# 1-Schematic_PCB.net
KiCad netlist of a schematic drawn in EasyEDA
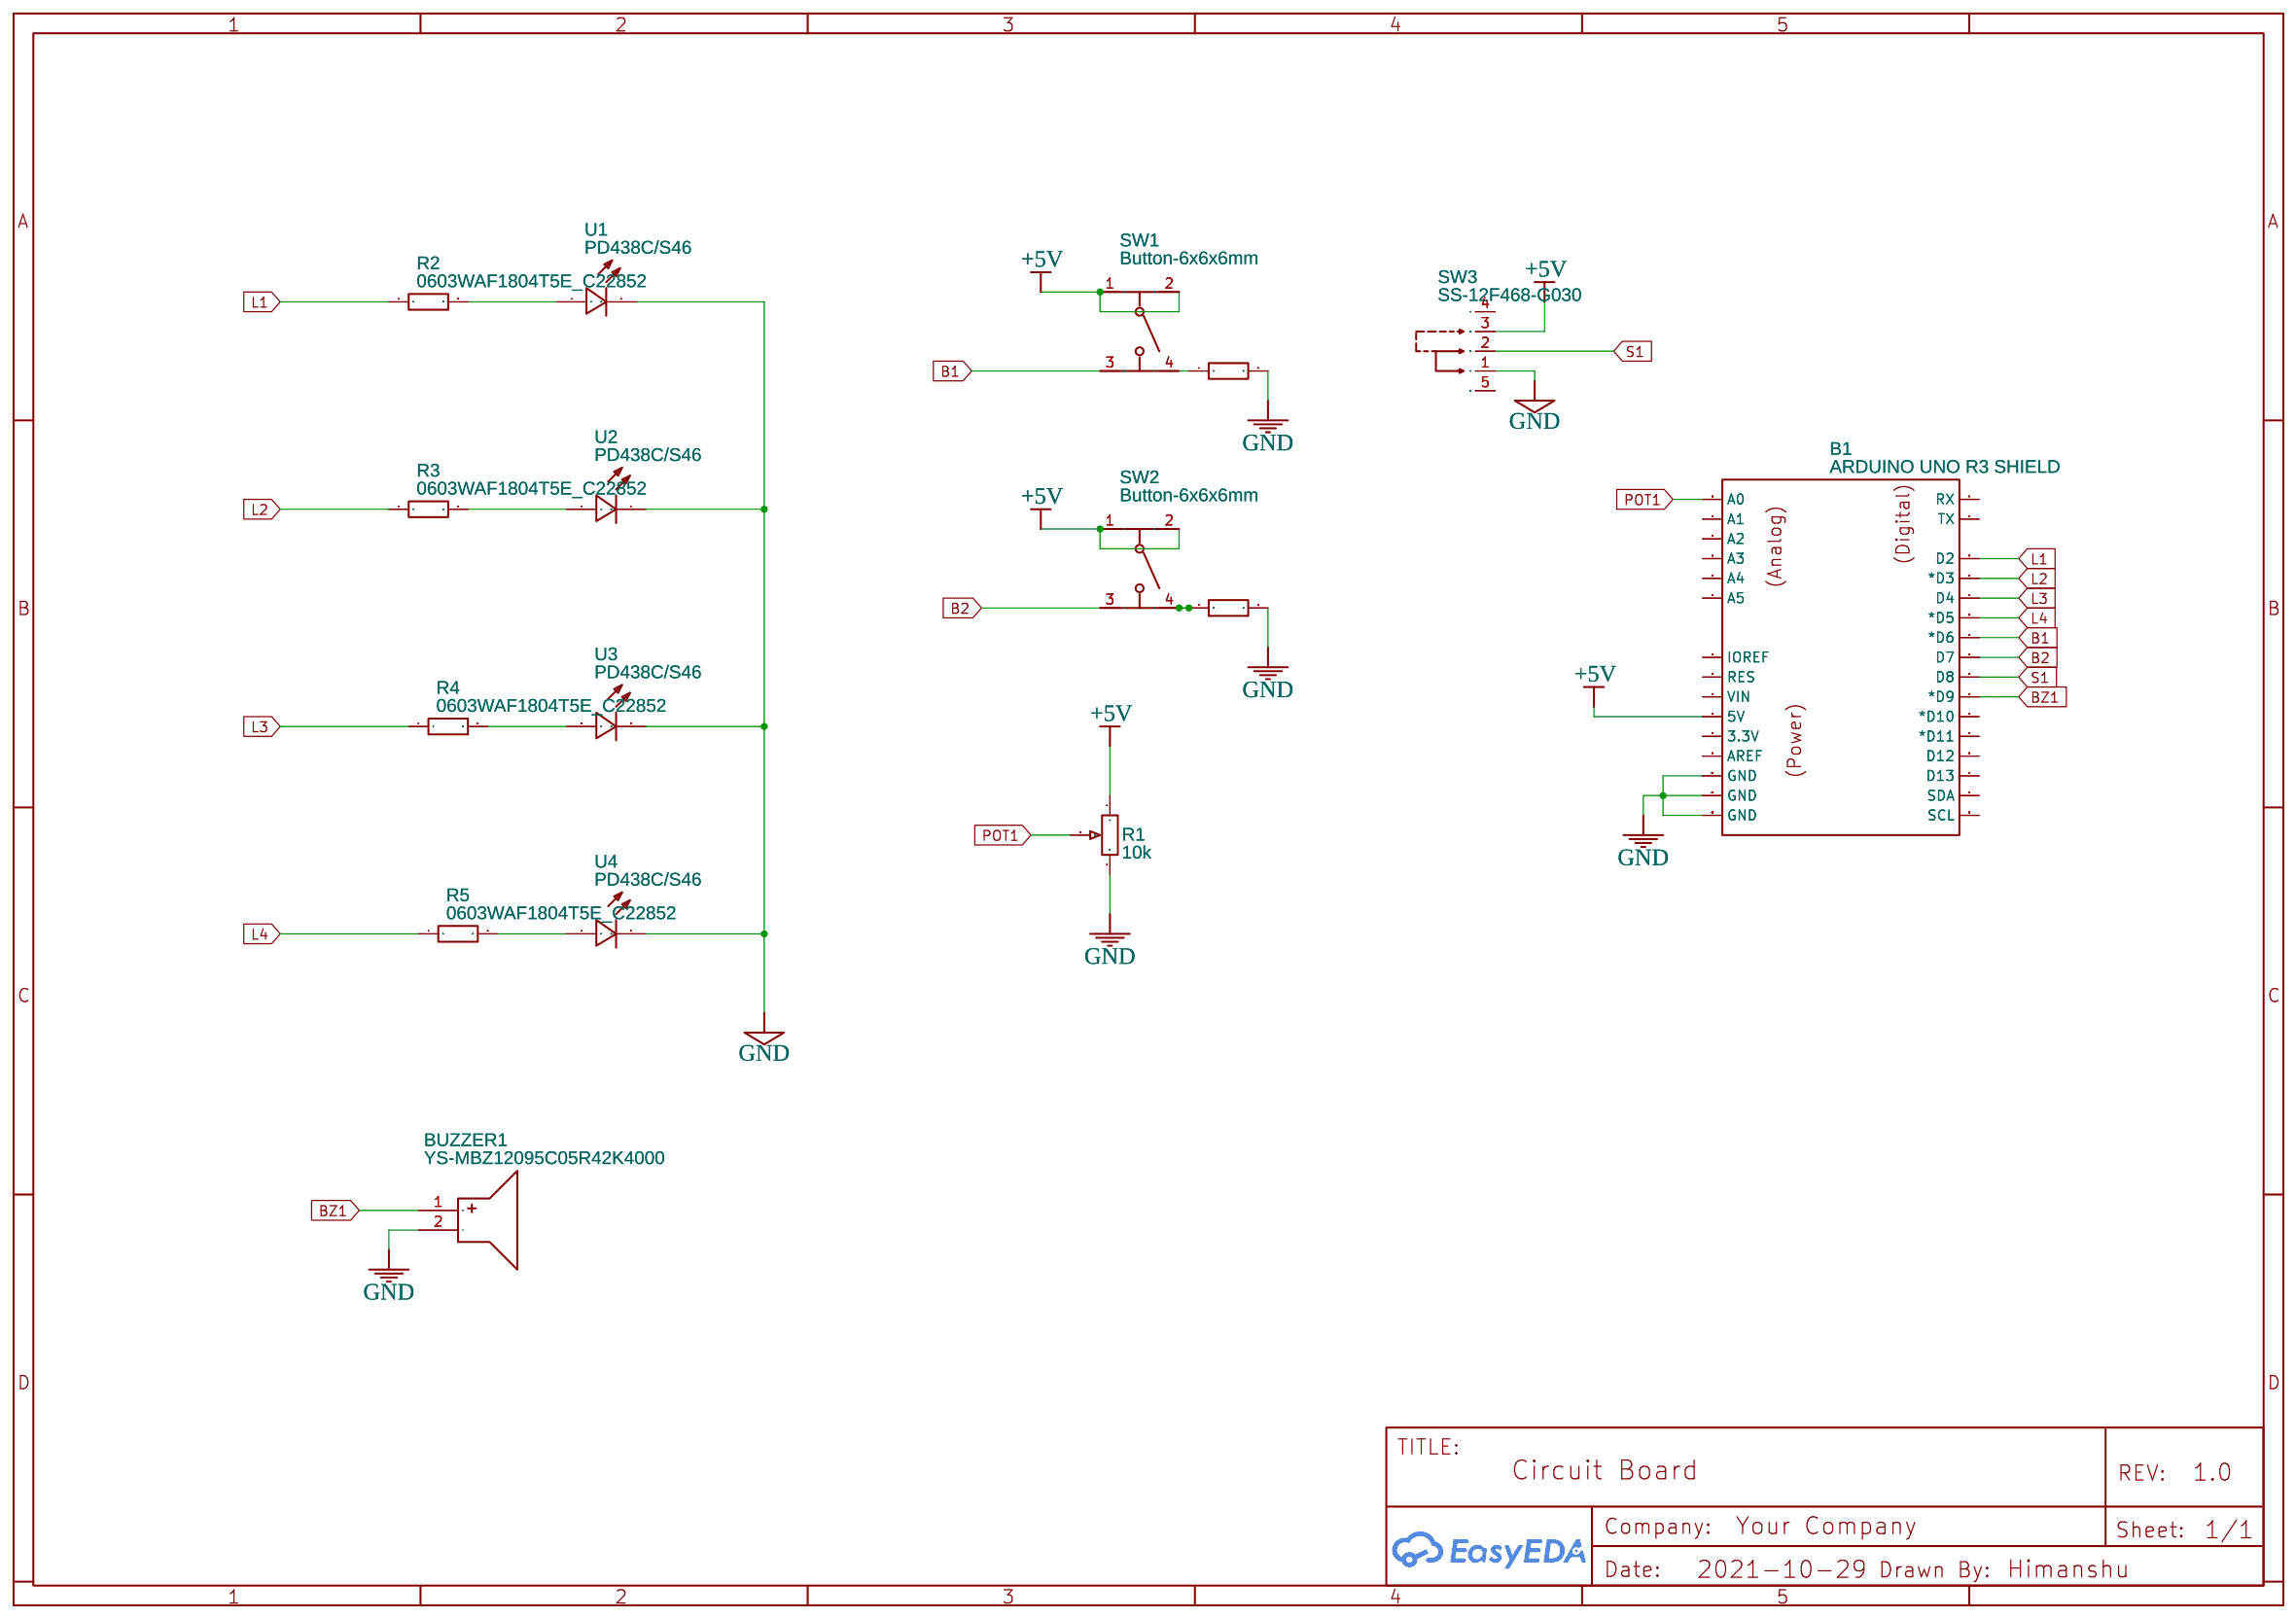
[diagram p0: schematic sheet]

(export (version "E")
  (design (tool "Eeschema 10.0.6"))
  (components
    (comp (ref "B1")
      (value "ARDUINO UNO R3 SHIELD")
      (fields (field (name "Manufacturer") "?"))
      (libsource (lib "") (part "ARDUINO UNO R3 SHIELD"))
    )
    (comp (ref "BUZZER1")
      (value "YS-MBZ12095C05R42K4000")
      (fields (field (name "BOM_Supplier Part") "C2891357"))
      (libsource (lib "") (part "YS-MBZ12095C05R42K4000"))
    )
    (comp (ref "R1")
      (value "10k")
      (fields
        (field (name "BOM_Manufacturer Part") "3362F-1-103LF")
        (field (name "BOM_Supplier Part") "3362F-1-103LF-ND")
      )
      (libsource (lib "") (part "3362F-1-103LF"))
    )
    (comp (ref "R2")
      (value "0603WAF1804T5E_C22852")
      (fields
        (field (name "BOM_Manufacturer Part") "0603WAF1804T5E")
        (field (name "BOM_Supplier Part") "C22852")
      )
      (libsource (lib "") (part "0603WAF1804T5E_C22852"))
    )
    (comp (ref "R3")
      (value "0603WAF1804T5E_C22852")
      (fields
        (field (name "BOM_Manufacturer Part") "0603WAF1804T5E")
        (field (name "BOM_Supplier Part") "C22852")
      )
      (libsource (lib "") (part "0603WAF1804T5E_C22852"))
    )
    (comp (ref "R4")
      (value "0603WAF1804T5E_C22852")
      (fields
        (field (name "BOM_Manufacturer Part") "0603WAF1804T5E")
        (field (name "BOM_Supplier Part") "C22852")
      )
      (libsource (lib "") (part "0603WAF1804T5E_C22852"))
    )
    (comp (ref "R5")
      (value "0603WAF1804T5E_C22852")
      (fields
        (field (name "BOM_Manufacturer Part") "0603WAF1804T5E")
        (field (name "BOM_Supplier Part") "C22852")
      )
      (libsource (lib "") (part "0603WAF1804T5E_C22852"))
    )
    (comp (ref "R6")
      (value "0603WAF1804T5E_C22852")
      (fields
        (field (name "BOM_Manufacturer Part") "0603WAF1804T5E")
        (field (name "BOM_Supplier Part") "C22852")
      )
      (libsource (lib "") (part "0603WAF1804T5E_C22852"))
    )
    (comp (ref "R7")
      (value "0603WAF1804T5E_C22852")
      (fields
        (field (name "BOM_Manufacturer Part") "0603WAF1804T5E")
        (field (name "BOM_Supplier Part") "C22852")
      )
      (libsource (lib "") (part "0603WAF1804T5E_C22852"))
    )
    (comp (ref "SW1")
      (value "Button-6x6x6mm")
      (fields
        (field (name "BOM_Manufacturer Part") "Switch,6*6*6Plastic head,260G, 0.25mm,Straight line")
        (field (name "BOM_Supplier Part") "C71836")
      )
      (libsource (lib "") (part "Button-6x6x6mm"))
    )
    (comp (ref "SW2")
      (value "Button-6x6x6mm")
      (fields
        (field (name "BOM_Manufacturer Part") "Switch,6*6*6Plastic head,260G, 0.25mm,Straight line")
        (field (name "BOM_Supplier Part") "C71836")
      )
      (libsource (lib "") (part "Button-6x6x6mm"))
    )
    (comp (ref "SW3")
      (value "SS-12F468-G030")
      (fields (field (name "BOM_Supplier Part") "C2848904"))
      (libsource (lib "") (part "SS-12F468-G030"))
    )
    (comp (ref "U1")
      (value "PD438C/S46")
      (fields (field (name "BOM_Supplier Part") "C146238"))
      (libsource (lib "") (part "PD438C/S46"))
    )
    (comp (ref "U2")
      (value "PD438C/S46")
      (fields (field (name "BOM_Supplier Part") "C146238"))
      (libsource (lib "") (part "PD438C/S46"))
    )
    (comp (ref "U3")
      (value "PD438C/S46")
      (fields (field (name "BOM_Supplier Part") "C146238"))
      (libsource (lib "") (part "PD438C/S46"))
    )
    (comp (ref "U4")
      (value "PD438C/S46")
      (fields (field (name "BOM_Supplier Part") "C146238"))
      (libsource (lib "") (part "PD438C/S46"))
    )
  )
  (nets
    (net (code "1") (name "+5V") (class "Default")
      (node (ref "B1") (pin "5V") (pinfunction "5V_5V") (pintype "unspecified"))
      (node (ref "R1") (pin "1") (pinfunction "1_1") (pintype "input"))
      (node (ref "SW1") (pin "1") (pinfunction "1_1") (pintype "unspecified"))
      (node (ref "SW1") (pin "2") (pinfunction "2_2") (pintype "unspecified"))
      (node (ref "SW2") (pin "1") (pinfunction "1_1") (pintype "unspecified"))
      (node (ref "SW2") (pin "2") (pinfunction "2_2") (pintype "unspecified"))
      (node (ref "SW3") (pin "3") (pinfunction "3_3") (pintype "unspecified"))
    )
    (net (code "2") (name "B1") (class "Default")
      (node (ref "B1") (pin "D6") (pinfunction "*D6_D6") (pintype "unspecified"))
      (node (ref "SW1") (pin "3") (pinfunction "3_3") (pintype "unspecified"))
    )
    (net (code "3") (name "B2") (class "Default")
      (node (ref "B1") (pin "D7") (pinfunction "D7_D7") (pintype "unspecified"))
      (node (ref "SW2") (pin "3") (pinfunction "3_3") (pintype "unspecified"))
    )
    (net (code "4") (name "BZ1") (class "Default")
      (node (ref "B1") (pin "D9") (pinfunction "*D9_D9") (pintype "unspecified"))
      (node (ref "BUZZER1") (pin "1") (pinfunction "+_1") (pintype "unspecified"))
    )
    (net (code "5") (name "GND") (class "Default")
      (node (ref "B1") (pin "GND@0") (pinfunction "GND_GND@0") (pintype "unspecified"))
      (node (ref "B1") (pin "GND@1") (pinfunction "GND_GND@1") (pintype "unspecified"))
      (node (ref "B1") (pin "GND@2") (pinfunction "GND_GND@2") (pintype "unspecified"))
      (node (ref "BUZZER1") (pin "2") (pinfunction "-_2") (pintype "unspecified"))
      (node (ref "R1") (pin "3") (pinfunction "3_3") (pintype "input"))
      (node (ref "R6") (pin "2") (pinfunction "2_2") (pintype "input"))
      (node (ref "R7") (pin "2") (pinfunction "2_2") (pintype "input"))
      (node (ref "SW3") (pin "1") (pinfunction "1_1") (pintype "unspecified"))
      (node (ref "U1") (pin "2") (pinfunction "C_2") (pintype "unspecified"))
      (node (ref "U2") (pin "2") (pinfunction "C_2") (pintype "unspecified"))
      (node (ref "U3") (pin "2") (pinfunction "C_2") (pintype "unspecified"))
      (node (ref "U4") (pin "2") (pinfunction "C_2") (pintype "unspecified"))
    )
    (net (code "6") (name "L1") (class "Default")
      (node (ref "B1") (pin "D2") (pinfunction "D2_D2") (pintype "unspecified"))
      (node (ref "R2") (pin "1") (pinfunction "1_1") (pintype "input"))
    )
    (net (code "7") (name "L2") (class "Default")
      (node (ref "B1") (pin "D3") (pinfunction "*D3_D3") (pintype "unspecified"))
      (node (ref "R3") (pin "1") (pinfunction "1_1") (pintype "input"))
    )
    (net (code "8") (name "L3") (class "Default")
      (node (ref "B1") (pin "D4") (pinfunction "D4_D4") (pintype "unspecified"))
      (node (ref "R4") (pin "1") (pinfunction "1_1") (pintype "input"))
    )
    (net (code "9") (name "L4") (class "Default")
      (node (ref "B1") (pin "D5") (pinfunction "*D5_D5") (pintype "unspecified"))
      (node (ref "R5") (pin "1") (pinfunction "1_1") (pintype "input"))
    )
    (net (code "10") (name "Net-(R6-Pad1)") (class "Default")
      (node (ref "R6") (pin "1") (pinfunction "1_1") (pintype "input"))
      (node (ref "SW1") (pin "4") (pinfunction "4_4") (pintype "unspecified"))
    )
    (net (code "11") (name "Net-(R7-Pad1)") (class "Default")
      (node (ref "R7") (pin "1") (pinfunction "1_1") (pintype "input"))
      (node (ref "SW2") (pin "4") (pinfunction "4_4") (pintype "unspecified"))
    )
    (net (code "12") (name "Net-(U1-A)") (class "Default")
      (node (ref "R2") (pin "2") (pinfunction "2_2") (pintype "input"))
      (node (ref "U1") (pin "1") (pinfunction "A_1") (pintype "unspecified"))
    )
    (net (code "13") (name "Net-(U2-A)") (class "Default")
      (node (ref "R3") (pin "2") (pinfunction "2_2") (pintype "input"))
      (node (ref "U2") (pin "1") (pinfunction "A_1") (pintype "unspecified"))
    )
    (net (code "14") (name "Net-(U3-A)") (class "Default")
      (node (ref "R4") (pin "2") (pinfunction "2_2") (pintype "input"))
      (node (ref "U3") (pin "1") (pinfunction "A_1") (pintype "unspecified"))
    )
    (net (code "15") (name "Net-(U4-A)") (class "Default")
      (node (ref "R5") (pin "2") (pinfunction "2_2") (pintype "input"))
      (node (ref "U4") (pin "1") (pinfunction "A_1") (pintype "unspecified"))
    )
    (net (code "16") (name "POT1") (class "Default")
      (node (ref "B1") (pin "A0") (pinfunction "A0_A0") (pintype "unspecified"))
      (node (ref "R1") (pin "2") (pinfunction "2_2") (pintype "input"))
    )
    (net (code "17") (name "S1") (class "Default")
      (node (ref "B1") (pin "D8") (pinfunction "D8_D8") (pintype "unspecified"))
      (node (ref "SW3") (pin "2") (pinfunction "2_2") (pintype "unspecified"))
    )
    (net (code "18") (name "unconnected-(B1-*D10-PadD10)") (class "Default")
      (node (ref "B1") (pin "D10") (pinfunction "*D10_D10") (pintype "unspecified"))
    )
    (net (code "19") (name "unconnected-(B1-*D11-PadD11)") (class "Default")
      (node (ref "B1") (pin "D11") (pinfunction "*D11_D11") (pintype "unspecified"))
    )
    (net (code "20") (name "unconnected-(B1-Pad3.3V)") (class "Default")
      (node (ref "B1") (pin "3.3V") (pinfunction "3.3V_3.3V") (pintype "unspecified"))
    )
    (net (code "21") (name "unconnected-(B1-PadA1)") (class "Default")
      (node (ref "B1") (pin "A1") (pinfunction "A1_A1") (pintype "unspecified"))
    )
    (net (code "22") (name "unconnected-(B1-PadA2)") (class "Default")
      (node (ref "B1") (pin "A2") (pinfunction "A2_A2") (pintype "unspecified"))
    )
    (net (code "23") (name "unconnected-(B1-PadA3)") (class "Default")
      (node (ref "B1") (pin "A3") (pinfunction "A3_A3") (pintype "unspecified"))
    )
    (net (code "24") (name "unconnected-(B1-PadA4)") (class "Default")
      (node (ref "B1") (pin "A4") (pinfunction "A4_A4") (pintype "unspecified"))
    )
    (net (code "25") (name "unconnected-(B1-PadA5)") (class "Default")
      (node (ref "B1") (pin "A5") (pinfunction "A5_A5") (pintype "unspecified"))
    )
    (net (code "26") (name "unconnected-(B1-PadAREF)") (class "Default")
      (node (ref "B1") (pin "AREF") (pinfunction "AREF_AREF") (pintype "unspecified"))
    )
    (net (code "27") (name "unconnected-(B1-PadD12)") (class "Default")
      (node (ref "B1") (pin "D12") (pinfunction "D12_D12") (pintype "unspecified"))
    )
    (net (code "28") (name "unconnected-(B1-PadD13)") (class "Default")
      (node (ref "B1") (pin "D13") (pinfunction "D13_D13") (pintype "unspecified"))
    )
    (net (code "29") (name "unconnected-(B1-PadIOREF)") (class "Default")
      (node (ref "B1") (pin "IOREF") (pinfunction "IOREF_IOREF") (pintype "unspecified"))
    )
    (net (code "30") (name "unconnected-(B1-PadRES)") (class "Default")
      (node (ref "B1") (pin "RES") (pinfunction "RES_RES") (pintype "unspecified"))
    )
    (net (code "31") (name "unconnected-(B1-PadRX)") (class "Default")
      (node (ref "B1") (pin "RX") (pinfunction "RX_RX") (pintype "unspecified"))
    )
    (net (code "32") (name "unconnected-(B1-PadSCL)") (class "Default")
      (node (ref "B1") (pin "SCL") (pinfunction "SCL_SCL") (pintype "unspecified"))
    )
    (net (code "33") (name "unconnected-(B1-PadSDA)") (class "Default")
      (node (ref "B1") (pin "SDA") (pinfunction "SDA_SDA") (pintype "unspecified"))
    )
    (net (code "34") (name "unconnected-(B1-PadTX)") (class "Default")
      (node (ref "B1") (pin "TX") (pinfunction "TX_TX") (pintype "unspecified"))
    )
    (net (code "35") (name "unconnected-(B1-PadVIN)") (class "Default")
      (node (ref "B1") (pin "VIN") (pinfunction "VIN_VIN") (pintype "unspecified"))
    )
    (net (code "36") (name "unconnected-(SW3-Pad4)") (class "Default")
      (node (ref "SW3") (pin "4") (pinfunction "4_4") (pintype "unspecified"))
    )
    (net (code "37") (name "unconnected-(SW3-Pad5)") (class "Default")
      (node (ref "SW3") (pin "5") (pinfunction "5_5") (pintype "unspecified"))
    )
  )
)
